# HS5035HD_Test_841.net
KiCad netlist of a schematic drawn in EAGLE
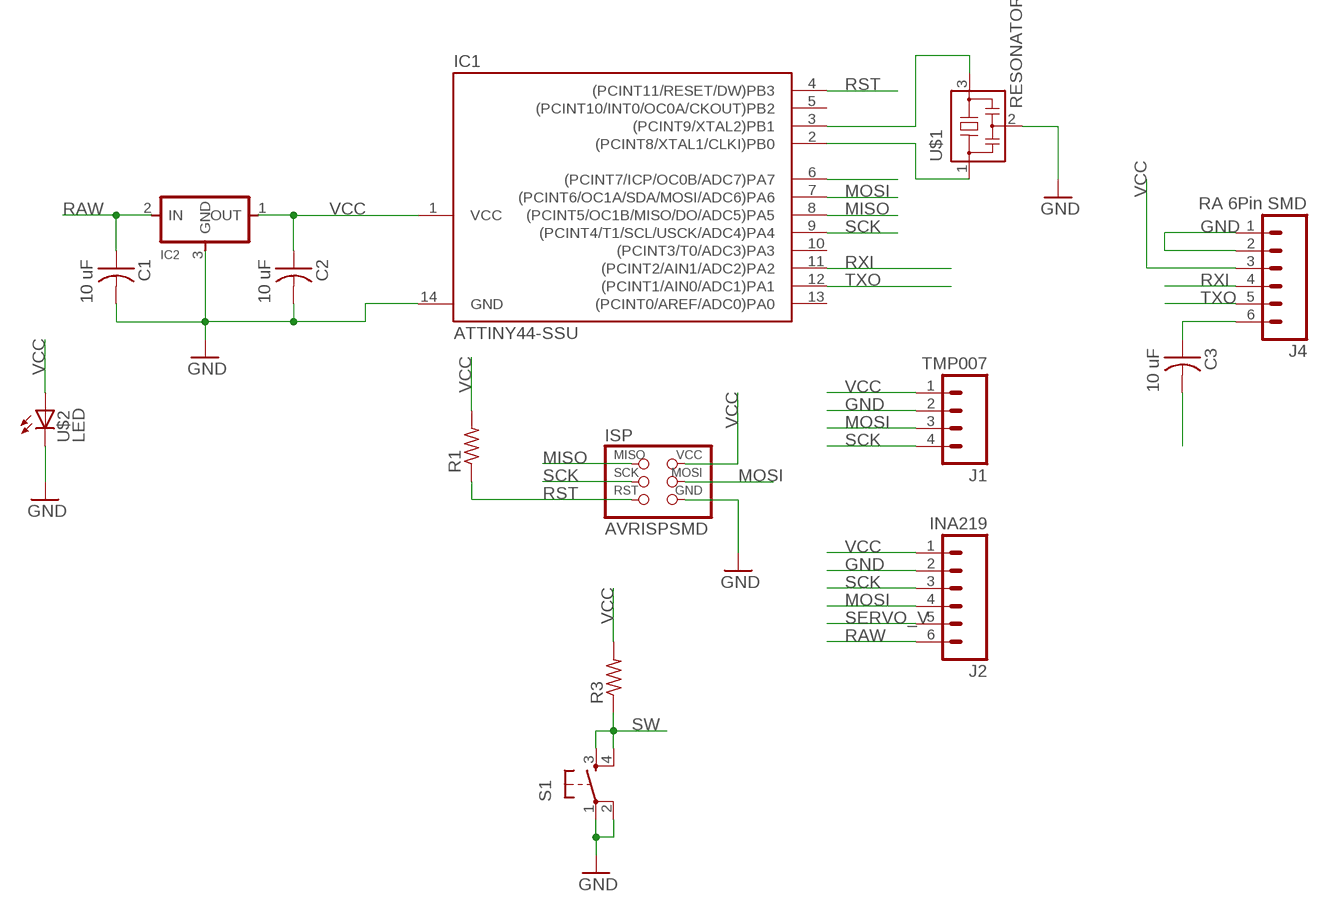
[diagram p0: schematic, sheet 1]

(export (version "E")
  (design (tool "Eeschema 10.0.6"))
  (components
    (comp (ref "C1")
      (value "10 uF")
      (footprint "eagle-import:C1206FAB")
      (libsource (lib "eagle-import") (part "CAP-US1206FAB"))
    )
    (comp (ref "C2")
      (value "10 uF")
      (footprint "eagle-import:C1206FAB")
      (libsource (lib "eagle-import") (part "CAP-US1206FAB"))
    )
    (comp (ref "C3")
      (value "10 uF")
      (footprint "eagle-import:C1206FAB")
      (libsource (lib "eagle-import") (part "CAP-US1206FAB"))
    )
    (comp (ref "IC1")
      (value "ATTINY44-SSU")
      (footprint "eagle-import:SOIC14")
      (libsource (lib "eagle-import") (part "ATTINY44-SSU"))
    )
    (comp (ref "IC2")
      (value "REGULATORSOT23")
      (footprint "eagle-import:SOT23")
      (libsource (lib "eagle-import") (part "REGULATORSOT23"))
    )
    (comp (ref "ISP")
      (value "AVRISPSMD")
      (footprint "eagle-import:2X03SMD")
      (libsource (lib "eagle-import") (part "AVRISPSMD"))
    )
    (comp (ref "J1")
      (value "TMP007")
      (footprint "eagle-import:1X04-SMD")
      (libsource (lib "eagle-import") (part "M04SMD"))
    )
    (comp (ref "J2")
      (value "INA219")
      (footprint "eagle-import:1X06-SMD")
      (libsource (lib "eagle-import") (part "M06SMD"))
    )
    (comp (ref "J4")
      (value "RA 6Pin SMD")
      (footprint "eagle-import:1X06-SMD")
      (libsource (lib "eagle-import") (part "M06SMD"))
    )
    (comp (ref "R1")
      (value "RES-US1206FAB")
      (footprint "eagle-import:R1206FAB")
      (libsource (lib "eagle-import") (part "RES-US1206FAB"))
    )
    (comp (ref "R3")
      (value "RES-US1206FAB")
      (footprint "eagle-import:R1206FAB")
      (libsource (lib "eagle-import") (part "RES-US1206FAB"))
    )
    (comp (ref "S1")
      (value "6MM_SWITCH6MM_SWITCH")
      (footprint "eagle-import:6MM_SWITCH")
      (libsource (lib "eagle-import") (part "6MM_SWITCH6MM_SWITCH"))
    )
    (comp (ref "U$1")
      (value "RESONATOR")
      (footprint "eagle-import:EFOBM")
      (libsource (lib "eagle-import") (part "RESONATOR"))
    )
    (comp (ref "U$2")
      (value "LED")
      (footprint "eagle-import:LED1206")
      (libsource (lib "eagle-import") (part "LED"))
    )
  )
  (nets
    (net (code "1") (name "/MISO") (class "Default")
      (node (ref "IC1") (pin "8") (pinfunction "(PCINT5/OC1B/MISO/DO/ADC5)PA5_8") (pintype "bidirectional"))
      (node (ref "ISP") (pin "1") (pinfunction "MISO_1") (pintype "passive"))
    )
    (net (code "2") (name "/MOSI") (class "Default")
      (node (ref "IC1") (pin "7") (pinfunction "(PCINT6/OC1A/SDA/MOSI/ADC6)PA6_7") (pintype "bidirectional"))
      (node (ref "ISP") (pin "4") (pinfunction "MOSI_4") (pintype "passive"))
      (node (ref "J1") (pin "3") (pinfunction "3_3") (pintype "passive"))
      (node (ref "J2") (pin "4") (pinfunction "4_4") (pintype "passive"))
    )
    (net (code "3") (name "/RAW") (class "Default")
      (node (ref "C1") (pin "1") (pinfunction "1_1") (pintype "passive"))
      (node (ref "IC2") (pin "2") (pinfunction "IN_2") (pintype "bidirectional"))
      (node (ref "J2") (pin "6") (pinfunction "6_6") (pintype "passive"))
    )
    (net (code "4") (name "/RST") (class "Default")
      (node (ref "C3") (pin "2") (pinfunction "2_2") (pintype "passive"))
      (node (ref "IC1") (pin "4") (pinfunction "(PCINT11/RESET/DW)PB3_4") (pintype "bidirectional"))
      (node (ref "ISP") (pin "5") (pinfunction "RST_5") (pintype "passive"))
      (node (ref "R1") (pin "1") (pinfunction "1_1") (pintype "passive"))
    )
    (net (code "5") (name "/RXI") (class "Default")
      (node (ref "IC1") (pin "11") (pinfunction "(PCINT2/AIN1/ADC2)PA2_11") (pintype "bidirectional"))
      (node (ref "J4") (pin "4") (pinfunction "4_4") (pintype "passive"))
    )
    (net (code "6") (name "/SCK") (class "Default")
      (node (ref "IC1") (pin "9") (pinfunction "(PCINT4/T1/SCL/USCK/ADC4)PA4_9") (pintype "bidirectional"))
      (node (ref "ISP") (pin "3") (pinfunction "SCK_3") (pintype "passive"))
      (node (ref "J1") (pin "4") (pinfunction "4_4") (pintype "passive"))
      (node (ref "J2") (pin "3") (pinfunction "3_3") (pintype "passive"))
    )
    (net (code "7") (name "/SERVO_V") (class "Default")
      (node (ref "J2") (pin "5") (pinfunction "5_5") (pintype "passive"))
    )
    (net (code "8") (name "/SW") (class "Default")
      (node (ref "IC1") (pin "6") (pinfunction "(PCINT7/ICP/OC0B/ADC7)PA7_6") (pintype "bidirectional"))
      (node (ref "R3") (pin "1") (pinfunction "1_1") (pintype "passive"))
      (node (ref "S1") (pin "3") (pinfunction "S_3") (pintype "passive"))
      (node (ref "S1") (pin "4") (pinfunction "S1_4") (pintype "passive"))
    )
    (net (code "9") (name "/TXO") (class "Default")
      (node (ref "IC1") (pin "12") (pinfunction "(PCINT1/AIN0/ADC1)PA1_12") (pintype "bidirectional"))
      (node (ref "J4") (pin "5") (pinfunction "5_5") (pintype "passive"))
    )
    (net (code "10") (name "/VCC") (class "Default")
      (node (ref "C2") (pin "1") (pinfunction "1_1") (pintype "passive"))
      (node (ref "IC1") (pin "1") (pinfunction "VCC_1") (pintype "power_in"))
      (node (ref "IC2") (pin "1") (pinfunction "OUT_1") (pintype "bidirectional"))
      (node (ref "ISP") (pin "2") (pinfunction "VCC_2") (pintype "passive"))
      (node (ref "J1") (pin "1") (pinfunction "1_1") (pintype "passive"))
      (node (ref "J2") (pin "1") (pinfunction "1_1") (pintype "passive"))
      (node (ref "J4") (pin "3") (pinfunction "3_3") (pintype "passive"))
      (node (ref "R1") (pin "2") (pinfunction "2_2") (pintype "passive"))
      (node (ref "R3") (pin "2") (pinfunction "2_2") (pintype "passive"))
      (node (ref "U$2") (pin "1") (pinfunction "A_1") (pintype "passive"))
    )
    (net (code "11") (name "GND") (class "Default")
      (node (ref "C1") (pin "2") (pinfunction "2_2") (pintype "passive"))
      (node (ref "C2") (pin "2") (pinfunction "2_2") (pintype "passive"))
      (node (ref "IC1") (pin "14") (pinfunction "GND_14") (pintype "power_in"))
      (node (ref "IC2") (pin "3") (pinfunction "GND_3") (pintype "bidirectional"))
      (node (ref "ISP") (pin "6") (pinfunction "GND_6") (pintype "passive"))
      (node (ref "J1") (pin "2") (pinfunction "2_2") (pintype "passive"))
      (node (ref "J2") (pin "2") (pinfunction "2_2") (pintype "passive"))
      (node (ref "J4") (pin "1") (pinfunction "1_1") (pintype "passive"))
      (node (ref "J4") (pin "2") (pinfunction "2_2") (pintype "passive"))
      (node (ref "S1") (pin "1") (pinfunction "P_1") (pintype "passive"))
      (node (ref "S1") (pin "2") (pinfunction "P1_2") (pintype "passive"))
      (node (ref "U$1") (pin "2") (pinfunction "2_2") (pintype "passive"))
      (node (ref "U$2") (pin "2") (pinfunction "C_2") (pintype "passive"))
    )
    (net (code "12") (name "Net-(C3-Pad1)") (class "Default")
      (node (ref "C3") (pin "1") (pinfunction "1_1") (pintype "passive"))
      (node (ref "J4") (pin "6") (pinfunction "6_6") (pintype "passive"))
    )
    (net (code "13") (name "Net-(IC1-(PCINT8{slash}XTAL1{slash}CLKI)PB0)") (class "Default")
      (node (ref "IC1") (pin "2") (pinfunction "(PCINT8/XTAL1/CLKI)PB0_2") (pintype "bidirectional"))
      (node (ref "U$1") (pin "1") (pinfunction "1_1") (pintype "passive"))
    )
    (net (code "14") (name "Net-(IC1-(PCINT9{slash}XTAL2)PB1)") (class "Default")
      (node (ref "IC1") (pin "3") (pinfunction "(PCINT9/XTAL2)PB1_3") (pintype "bidirectional"))
      (node (ref "U$1") (pin "3") (pinfunction "3_3") (pintype "passive"))
    )
    (net (code "15") (name "unconnected-(IC1-(PCINT0{slash}AREF{slash}ADC0)PA0-Pad13)") (class "Default")
      (node (ref "IC1") (pin "13") (pinfunction "(PCINT0/AREF/ADC0)PA0_13") (pintype "bidirectional"))
    )
    (net (code "16") (name "unconnected-(IC1-(PCINT3{slash}T0{slash}ADC3)PA3-Pad10)") (class "Default")
      (node (ref "IC1") (pin "10") (pinfunction "(PCINT3/T0/ADC3)PA3_10") (pintype "bidirectional"))
    )
    (net (code "17") (name "unconnected-(IC1-(PCINT10{slash}INT0{slash}OC0A{slash}CKOUT)PB2-Pad5)") (class "Default")
      (node (ref "IC1") (pin "5") (pinfunction "(PCINT10/INT0/OC0A/CKOUT)PB2_5") (pintype "bidirectional"))
    )
  )
)
